# heater.net
KiCad netlist of a schematic drawn in EAGLE
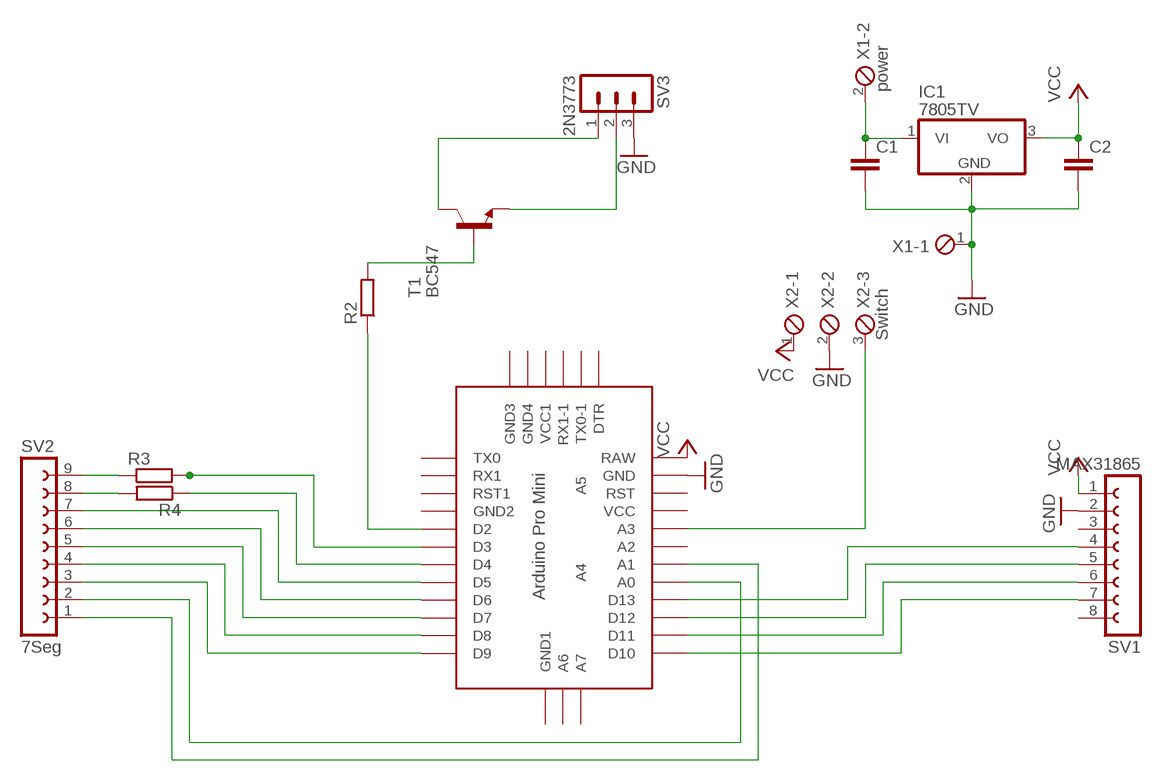
[diagram p0: schematic, sheet 1]

(export (version "E")
  (design (tool "Eeschema 10.0.6"))
  (components
    (comp (ref "C1")
      (value "C-EU025-050X050")
      (footprint "eagle-import:C025-050X050")
      (libsource (lib "eagle-import") (part "C-EU025-050X050"))
    )
    (comp (ref "C2")
      (value "C-EU025-050X050")
      (footprint "eagle-import:C025-050X050")
      (libsource (lib "eagle-import") (part "C-EU025-050X050"))
    )
    (comp (ref "IC1")
      (value "7805TV")
      (footprint "eagle-import:TO220V")
      (libsource (lib "eagle-import") (part "78TV05"))
    )
    (comp (ref "R2")
      (value "R-EU_0207/10")
      (footprint "eagle-import:0207_10")
      (libsource (lib "eagle-import") (part "R-EU_0207/10"))
    )
    (comp (ref "R3")
      (value "R-EU_0207/10")
      (footprint "eagle-import:0207_10")
      (libsource (lib "eagle-import") (part "R-EU_0207/10"))
    )
    (comp (ref "R4")
      (value "R-EU_0207/10")
      (footprint "eagle-import:0207_10")
      (libsource (lib "eagle-import") (part "R-EU_0207/10"))
    )
    (comp (ref "SV1")
      (value "MAX31865")
      (footprint "eagle-import:FE08")
      (libsource (lib "eagle-import") (part "FE08-1"))
    )
    (comp (ref "SV2")
      (value "7Seg")
      (footprint "eagle-import:FE09")
      (libsource (lib "eagle-import") (part "FE09-1"))
    )
    (comp (ref "SV3")
      (value "2N3773")
      (footprint "eagle-import:MA03-1")
      (libsource (lib "eagle-import") (part "MA03-1"))
    )
    (comp (ref "T1")
      (value "BC547")
      (footprint "eagle-import:TO92")
      (libsource (lib "eagle-import") (part "BC547"))
    )
    (comp (ref "U$1")
      (value "ABK-PRO-MINI")
      (footprint "eagle-import:ABK-PRO-MINI")
      (libsource (lib "eagle-import") (part "ABK-PRO-MINI"))
    )
    (comp (ref "X1")
      (value "power")
      (footprint "eagle-import:2POL254")
      (libsource (lib "eagle-import") (part "MPT2"))
    )
    (comp (ref "X2")
      (value "Switch")
      (footprint "eagle-import:3POL254")
      (libsource (lib "eagle-import") (part "MPT3"))
    )
  )
  (nets
    (net (code "1") (name "GND") (class "Default")
      (node (ref "C1") (pin "2") (pinfunction "2_2") (pintype "passive"))
      (node (ref "C2") (pin "2") (pinfunction "2_2") (pintype "passive"))
      (node (ref "IC1") (pin "2") (pinfunction "GND_2") (pintype "passive"))
      (node (ref "SV1") (pin "2") (pinfunction "2_2") (pintype "passive"))
      (node (ref "SV3") (pin "3") (pinfunction "3_3") (pintype "passive"))
      (node (ref "U$1") (pin "GND") (pinfunction "GND_GND") (pintype "bidirectional"))
      (node (ref "X1") (pin "1") (pinfunction "1_1") (pintype "passive"))
      (node (ref "X2") (pin "2") (pinfunction "1_2") (pintype "passive"))
    )
    (net (code "2") (name "Net-(IC1-VI)") (class "Default")
      (node (ref "C1") (pin "1") (pinfunction "1_1") (pintype "passive"))
      (node (ref "IC1") (pin "1") (pinfunction "VI_1") (pintype "input"))
      (node (ref "X1") (pin "2") (pinfunction "1_2") (pintype "passive"))
    )
    (net (code "3") (name "Net-(R2-Pad1)") (class "Default")
      (node (ref "R2") (pin "1") (pinfunction "1_1") (pintype "passive"))
      (node (ref "U$1") (pin "D2") (pinfunction "D2_D2") (pintype "bidirectional"))
    )
    (net (code "4") (name "Net-(R3-Pad1)") (class "Default")
      (node (ref "R3") (pin "1") (pinfunction "1_1") (pintype "passive"))
      (node (ref "SV2") (pin "9") (pinfunction "9_9") (pintype "passive"))
    )
    (net (code "5") (name "Net-(R3-Pad2)") (class "Default")
      (node (ref "R3") (pin "2") (pinfunction "2_2") (pintype "passive"))
      (node (ref "U$1") (pin "D3") (pinfunction "D3_D3") (pintype "bidirectional"))
    )
    (net (code "6") (name "Net-(R4-Pad1)") (class "Default")
      (node (ref "R4") (pin "1") (pinfunction "1_1") (pintype "passive"))
      (node (ref "U$1") (pin "D4") (pinfunction "D4_D4") (pintype "bidirectional"))
    )
    (net (code "7") (name "Net-(R4-Pad2)") (class "Default")
      (node (ref "R4") (pin "2") (pinfunction "2_2") (pintype "passive"))
      (node (ref "SV2") (pin "8") (pinfunction "8_8") (pintype "passive"))
    )
    (net (code "8") (name "Net-(SV1-Pad4)") (class "Default")
      (node (ref "SV1") (pin "4") (pinfunction "4_4") (pintype "passive"))
      (node (ref "U$1") (pin "D13") (pinfunction "D13_D13") (pintype "bidirectional"))
    )
    (net (code "9") (name "Net-(SV1-Pad5)") (class "Default")
      (node (ref "SV1") (pin "5") (pinfunction "5_5") (pintype "passive"))
      (node (ref "U$1") (pin "D12") (pinfunction "D12_D12") (pintype "bidirectional"))
    )
    (net (code "10") (name "Net-(SV1-Pad6)") (class "Default")
      (node (ref "SV1") (pin "6") (pinfunction "6_6") (pintype "passive"))
      (node (ref "U$1") (pin "D11") (pinfunction "D11_D11") (pintype "bidirectional"))
    )
    (net (code "11") (name "Net-(SV1-Pad7)") (class "Default")
      (node (ref "SV1") (pin "7") (pinfunction "7_7") (pintype "passive"))
      (node (ref "U$1") (pin "D10") (pinfunction "D10_D10") (pintype "bidirectional"))
    )
    (net (code "12") (name "Net-(SV2-Pad1)") (class "Default")
      (node (ref "SV2") (pin "1") (pinfunction "1_1") (pintype "passive"))
      (node (ref "U$1") (pin "A1") (pinfunction "A1_A1") (pintype "bidirectional"))
    )
    (net (code "13") (name "Net-(SV2-Pad2)") (class "Default")
      (node (ref "SV2") (pin "2") (pinfunction "2_2") (pintype "passive"))
      (node (ref "U$1") (pin "A0") (pinfunction "A0_A0") (pintype "bidirectional"))
    )
    (net (code "14") (name "Net-(SV2-Pad3)") (class "Default")
      (node (ref "SV2") (pin "3") (pinfunction "3_3") (pintype "passive"))
      (node (ref "U$1") (pin "D9") (pinfunction "D9_D9") (pintype "bidirectional"))
    )
    (net (code "15") (name "Net-(SV2-Pad4)") (class "Default")
      (node (ref "SV2") (pin "4") (pinfunction "4_4") (pintype "passive"))
      (node (ref "U$1") (pin "D8") (pinfunction "D8_D8") (pintype "bidirectional"))
    )
    (net (code "16") (name "Net-(SV2-Pad5)") (class "Default")
      (node (ref "SV2") (pin "5") (pinfunction "5_5") (pintype "passive"))
      (node (ref "U$1") (pin "D7") (pinfunction "D7_D7") (pintype "bidirectional"))
    )
    (net (code "17") (name "Net-(SV2-Pad6)") (class "Default")
      (node (ref "SV2") (pin "6") (pinfunction "6_6") (pintype "passive"))
      (node (ref "U$1") (pin "D6") (pinfunction "D6_D6") (pintype "bidirectional"))
    )
    (net (code "18") (name "Net-(SV2-Pad7)") (class "Default")
      (node (ref "SV2") (pin "7") (pinfunction "7_7") (pintype "passive"))
      (node (ref "U$1") (pin "D5") (pinfunction "D5_D5") (pintype "bidirectional"))
    )
    (net (code "19") (name "Net-(T1-B)") (class "Default")
      (node (ref "R2") (pin "2") (pinfunction "2_2") (pintype "passive"))
      (node (ref "T1") (pin "2") (pinfunction "B_2") (pintype "passive"))
    )
    (net (code "20") (name "Net-(T1-C)") (class "Default")
      (node (ref "SV3") (pin "1") (pinfunction "1_1") (pintype "passive"))
      (node (ref "T1") (pin "3") (pinfunction "C_3") (pintype "passive"))
    )
    (net (code "21") (name "Net-(T1-E)") (class "Default")
      (node (ref "SV3") (pin "2") (pinfunction "2_2") (pintype "passive"))
      (node (ref "T1") (pin "1") (pinfunction "E_1") (pintype "passive"))
    )
    (net (code "22") (name "Net-(X2C-1)") (class "Default")
      (node (ref "U$1") (pin "A3") (pinfunction "A3_A3") (pintype "bidirectional"))
      (node (ref "X2") (pin "3") (pinfunction "1_3") (pintype "passive"))
    )
    (net (code "23") (name "VCC") (class "Default")
      (node (ref "C2") (pin "1") (pinfunction "1_1") (pintype "passive"))
      (node (ref "IC1") (pin "3") (pinfunction "VO_3") (pintype "passive"))
      (node (ref "SV1") (pin "1") (pinfunction "1_1") (pintype "passive"))
      (node (ref "U$1") (pin "RAW") (pinfunction "RAW_RAW") (pintype "bidirectional"))
      (node (ref "X2") (pin "1") (pinfunction "1_1") (pintype "passive"))
    )
    (net (code "24") (name "unconnected-(SV1-Pad3)") (class "Default")
      (node (ref "SV1") (pin "3") (pinfunction "3_3") (pintype "passive"))
    )
    (net (code "25") (name "unconnected-(SV1-Pad8)") (class "Default")
      (node (ref "SV1") (pin "8") (pinfunction "8_8") (pintype "passive"))
    )
    (net (code "26") (name "unconnected-(U$1-GND1-PadGND4)") (class "Default")
      (node (ref "U$1") (pin "GND4") (pinfunction "GND1_GND4") (pintype "bidirectional"))
    )
    (net (code "27") (name "unconnected-(U$1-GND2-PadGND1)") (class "Default")
      (node (ref "U$1") (pin "GND1") (pinfunction "GND2_GND1") (pintype "bidirectional"))
    )
    (net (code "28") (name "unconnected-(U$1-GND3-PadGND2)") (class "Default")
      (node (ref "U$1") (pin "GND2") (pinfunction "GND3_GND2") (pintype "bidirectional"))
    )
    (net (code "29") (name "unconnected-(U$1-GND4-PadGND3)") (class "Default")
      (node (ref "U$1") (pin "GND3") (pinfunction "GND4_GND3") (pintype "bidirectional"))
    )
    (net (code "30") (name "unconnected-(U$1-PadA2)") (class "Default")
      (node (ref "U$1") (pin "A2") (pinfunction "A2_A2") (pintype "bidirectional"))
    )
    (net (code "31") (name "unconnected-(U$1-PadA4)") (class "Default")
      (node (ref "U$1") (pin "A4") (pinfunction "A4_A4") (pintype "bidirectional"))
    )
    (net (code "32") (name "unconnected-(U$1-PadA5)") (class "Default")
      (node (ref "U$1") (pin "A5") (pinfunction "A5_A5") (pintype "bidirectional"))
    )
    (net (code "33") (name "unconnected-(U$1-PadA6)") (class "Default")
      (node (ref "U$1") (pin "A6") (pinfunction "A6_A6") (pintype "bidirectional"))
    )
    (net (code "34") (name "unconnected-(U$1-PadA7)") (class "Default")
      (node (ref "U$1") (pin "A7") (pinfunction "A7_A7") (pintype "bidirectional"))
    )
    (net (code "35") (name "unconnected-(U$1-PadDTR)") (class "Default")
      (node (ref "U$1") (pin "DTR") (pinfunction "DTR_DTR") (pintype "bidirectional"))
    )
    (net (code "36") (name "unconnected-(U$1-PadRST)") (class "Default")
      (node (ref "U$1") (pin "RST") (pinfunction "RST_RST") (pintype "bidirectional"))
    )
    (net (code "37") (name "unconnected-(U$1-PadRST1)") (class "Default")
      (node (ref "U$1") (pin "RST1") (pinfunction "RST1_RST1") (pintype "bidirectional"))
    )
    (net (code "38") (name "unconnected-(U$1-PadRX1)") (class "Default")
      (node (ref "U$1") (pin "RX1") (pinfunction "RX1_RX1") (pintype "bidirectional"))
    )
    (net (code "39") (name "unconnected-(U$1-PadRX1-1)") (class "Default")
      (node (ref "U$1") (pin "RX1-1") (pinfunction "RX1-1_RX1-1") (pintype "bidirectional"))
    )
    (net (code "40") (name "unconnected-(U$1-PadTX0)") (class "Default")
      (node (ref "U$1") (pin "TX0") (pinfunction "TX0_TX0") (pintype "bidirectional"))
    )
    (net (code "41") (name "unconnected-(U$1-PadTX0-1)") (class "Default")
      (node (ref "U$1") (pin "TX0-1") (pinfunction "TX0-1_TX0-1") (pintype "bidirectional"))
    )
    (net (code "42") (name "unconnected-(U$1-PadVCC)") (class "Default")
      (node (ref "U$1") (pin "VCC") (pinfunction "VCC_VCC") (pintype "bidirectional"))
    )
    (net (code "43") (name "unconnected-(U$1-PadVCC1)") (class "Default")
      (node (ref "U$1") (pin "VCC1") (pinfunction "VCC1_VCC1") (pintype "bidirectional"))
    )
  )
)
